# MCP3202.net
KiCad netlist of a schematic drawn in Altium Designer
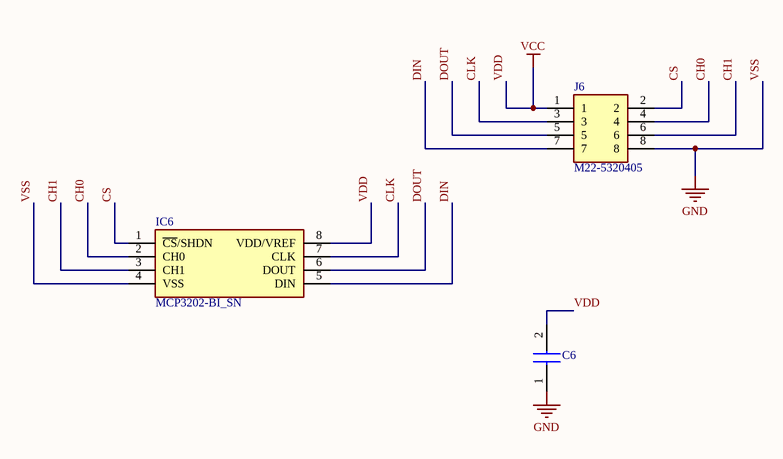
[diagram p0: MCP3202.SchDoc]

(export (version "E")
  (design (tool "Eeschema 10.0.6"))
  (components
    (comp (ref "C6")
      (value "GRM21BR71C105MA01K")
      (footprint "SamacSys:CAPC2012X145N")
      (description "Capacitor")
      (fields (field (name "MOUSER PART NUMBER") "81-GRM21R71C105MA01K"))
      (libsource (lib "*") (part "GRM21BR71C105MA01K"))
    )
    (comp (ref "IC6")
      (value "MCP3202-BI_SN")
      (footprint "SamacSys:SOIC127P600X175-8N")
      (description "Integrated Circuit")
      (fields
        (field (name "MANUFACTURER_PART_NUMBER") "MCP3202-BI/SN")
        (field (name "MOUSER PART NUMBER") "579-MCP3202BISN")
      )
      (libsource (lib "*") (part "MCP3202-BI_SN"))
    )
    (comp (ref "J6")
      (value "M22-5320405")
      (footprint "SamacSys:HUSSP8W50P200_2X4_800X400X500P")
      (description "Connector")
      (fields (field (name "MOUSER PART NUMBER") "855-M22-5320405"))
      (libsource (lib "*") (part "M22-5320405"))
    )
  )
  (nets
    (net (code "1") (name "/CH0") (class "Default")
      (node (ref "IC6") (pin "2") (pinfunction "CH0_2") (pintype "passive"))
      (node (ref "J6") (pin "4") (pinfunction "4_4") (pintype "passive"))
    )
    (net (code "2") (name "/CH1") (class "Default")
      (node (ref "IC6") (pin "3") (pinfunction "CH1_3") (pintype "passive"))
      (node (ref "J6") (pin "6") (pinfunction "6_6") (pintype "passive"))
    )
    (net (code "3") (name "/CLK") (class "Default")
      (node (ref "IC6") (pin "7") (pinfunction "CLK_7") (pintype "passive"))
      (node (ref "J6") (pin "3") (pinfunction "3_3") (pintype "passive"))
    )
    (net (code "4") (name "/CS") (class "Default")
      (node (ref "IC6") (pin "1") (pinfunction "~{CS}/SHDN_1") (pintype "passive"))
      (node (ref "J6") (pin "2") (pinfunction "2_2") (pintype "passive"))
    )
    (net (code "5") (name "/DIN") (class "Default")
      (node (ref "IC6") (pin "5") (pinfunction "DIN_5") (pintype "passive"))
      (node (ref "J6") (pin "7") (pinfunction "7_7") (pintype "passive"))
    )
    (net (code "6") (name "/DOUT") (class "Default")
      (node (ref "IC6") (pin "6") (pinfunction "DOUT_6") (pintype "passive"))
      (node (ref "J6") (pin "5") (pinfunction "5_5") (pintype "passive"))
    )
    (net (code "7") (name "GND") (class "Default")
      (node (ref "C6") (pin "1") (pinfunction "1_1") (pintype "passive"))
      (node (ref "IC6") (pin "4") (pinfunction "VSS_4") (pintype "passive"))
      (node (ref "J6") (pin "8") (pinfunction "8_8") (pintype "passive"))
    )
    (net (code "8") (name "VCC") (class "Default")
      (node (ref "C6") (pin "2") (pinfunction "2_2") (pintype "passive"))
      (node (ref "IC6") (pin "8") (pinfunction "VDD/VREF_8") (pintype "passive"))
      (node (ref "J6") (pin "1") (pinfunction "1_1") (pintype "passive"))
    )
  )
)
